# OBC_EBI_D-Latch.net
KiCad netlist of a schematic drawn in Altium Designer
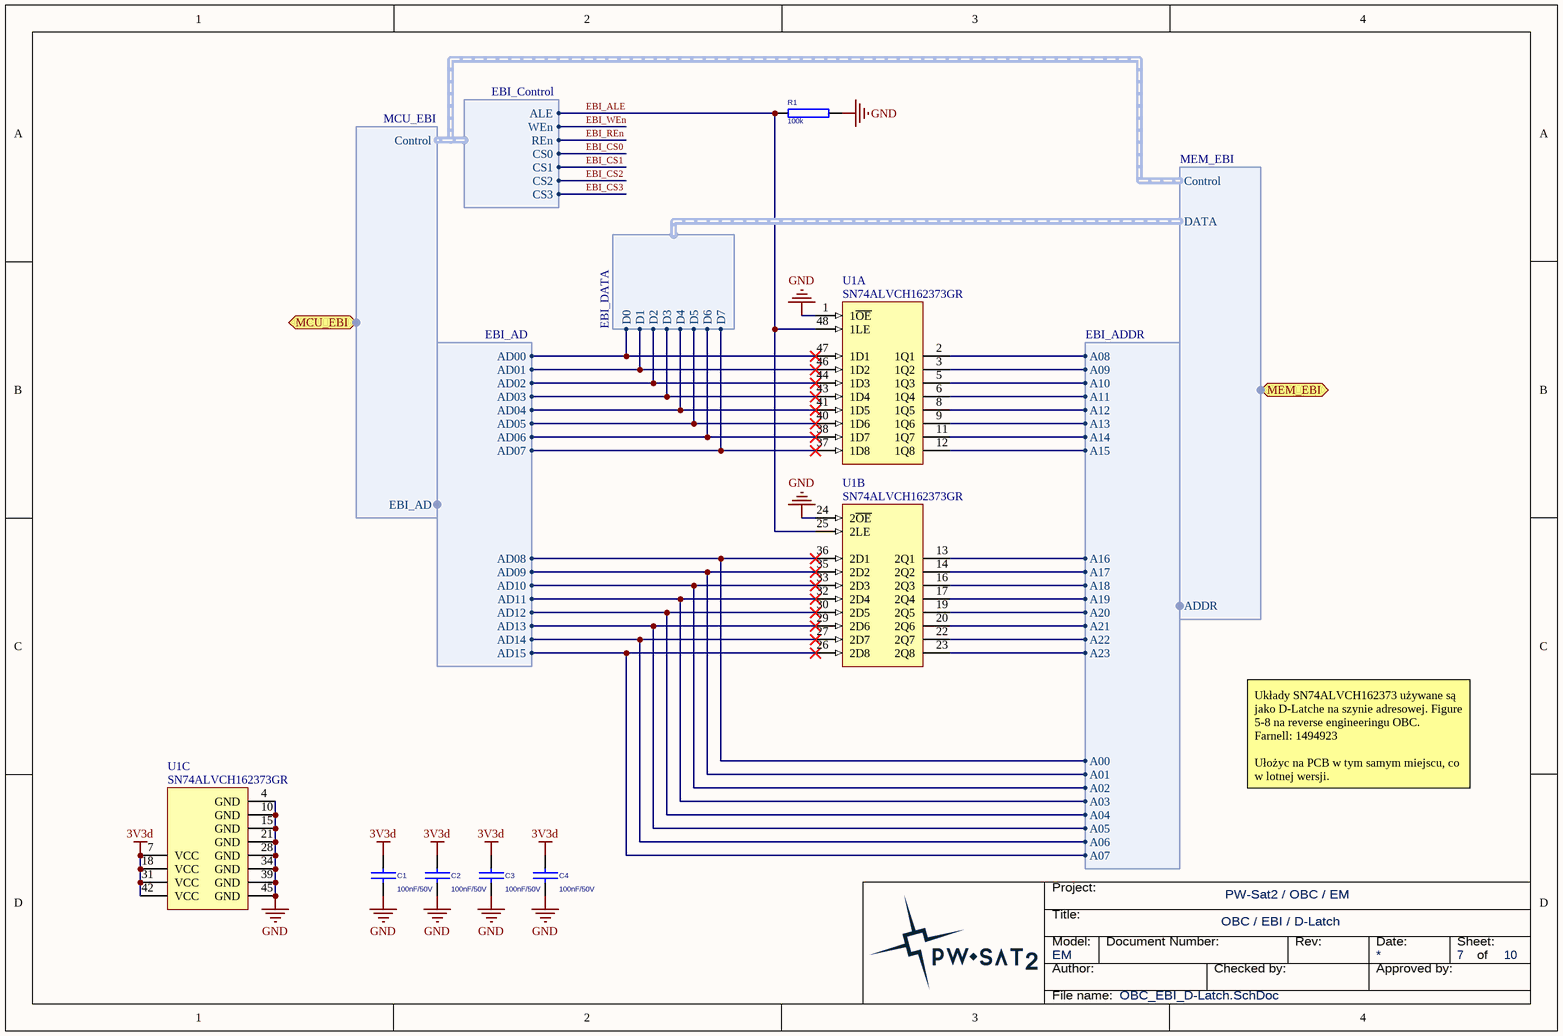
[diagram p0: OBC_EBI_D-Latch.SchDoc]

(export (version "E")
  (design (tool "Eeschema 10.0.6"))
  (components
    (comp (ref "C1")
      (value "100nF/50V")
      (footprint "C0603")
      (description "Capacitator")
      (fields (field (name "VOLTAGE") "50V"))
      (libsource (lib "SchLib") (part "CAP"))
    )
    (comp (ref "C2")
      (value "100nF/50V")
      (footprint "C0603")
      (description "Capacitator")
      (fields (field (name "VOLTAGE") "50V"))
      (libsource (lib "SchLib") (part "CAP"))
    )
    (comp (ref "C3")
      (value "100nF/50V")
      (footprint "C0603")
      (description "Capacitator")
      (fields (field (name "VOLTAGE") "50V"))
      (libsource (lib "SchLib") (part "CAP"))
    )
    (comp (ref "C4")
      (value "100nF/50V")
      (footprint "C0603")
      (description "Capacitator")
      (fields (field (name "VOLTAGE") "50V"))
      (libsource (lib "SchLib") (part "CAP"))
    )
    (comp (ref "R1")
      (value "100k")
      (footprint "R0603")
      (description "Resistor")
      (fields (field (name "TOLERANCE") "1%"))
      (libsource (lib "SchLib") (part "RES"))
    )
    (comp (ref "U1")
      (value "SN74ALVCH162373GR")
      (footprint "DGG0048A_N")
      (description "16-Bit Transparent D-Type Latch with 3-State Outputs, DGG0048A, LARGE T&R")
      (fields (field (name "MANUFACTURER") "Texas Instruments"))
      (libsource (lib "OBC") (part "SN74ALVCH162373GR"))
    )
  )
  (nets
    (net (code "5") (name "/A00") (class "Default")
      (node (ref "U1") (pin "36") (pinfunction "2D1_36") (pintype "input+no_connect"))
    )
    (net (code "6") (name "/A01") (class "Default")
      (node (ref "U1") (pin "35") (pinfunction "2D2_35") (pintype "input+no_connect"))
    )
    (net (code "7") (name "/A02") (class "Default")
      (node (ref "U1") (pin "33") (pinfunction "2D3_33") (pintype "input+no_connect"))
    )
    (net (code "8") (name "/A03") (class "Default")
      (node (ref "U1") (pin "32") (pinfunction "2D4_32") (pintype "input+no_connect"))
    )
    (net (code "9") (name "/A04") (class "Default")
      (node (ref "U1") (pin "30") (pinfunction "2D5_30") (pintype "input+no_connect"))
    )
    (net (code "10") (name "/A05") (class "Default")
      (node (ref "U1") (pin "29") (pinfunction "2D6_29") (pintype "input+no_connect"))
    )
    (net (code "11") (name "/A06") (class "Default")
      (node (ref "U1") (pin "27") (pinfunction "2D7_27") (pintype "input+no_connect"))
    )
    (net (code "12") (name "/A07") (class "Default")
      (node (ref "U1") (pin "26") (pinfunction "2D8_26") (pintype "input+no_connect"))
    )
    (net (code "13") (name "/A08") (class "Default")
      (node (ref "U1") (pin "2") (pinfunction "1Q1_2") (pintype "tri_state"))
    )
    (net (code "14") (name "/A09") (class "Default")
      (node (ref "U1") (pin "3") (pinfunction "1Q2_3") (pintype "tri_state"))
    )
    (net (code "15") (name "/A10") (class "Default")
      (node (ref "U1") (pin "5") (pinfunction "1Q3_5") (pintype "tri_state"))
    )
    (net (code "16") (name "/A11") (class "Default")
      (node (ref "U1") (pin "6") (pinfunction "1Q4_6") (pintype "tri_state"))
    )
    (net (code "17") (name "/A12") (class "Default")
      (node (ref "U1") (pin "8") (pinfunction "1Q5_8") (pintype "tri_state"))
    )
    (net (code "18") (name "/A13") (class "Default")
      (node (ref "U1") (pin "9") (pinfunction "1Q6_9") (pintype "tri_state"))
    )
    (net (code "19") (name "/A14") (class "Default")
      (node (ref "U1") (pin "11") (pinfunction "1Q7_11") (pintype "tri_state"))
    )
    (net (code "20") (name "/A15") (class "Default")
      (node (ref "U1") (pin "12") (pinfunction "1Q8_12") (pintype "tri_state"))
    )
    (net (code "21") (name "/A16") (class "Default")
      (node (ref "U1") (pin "13") (pinfunction "2Q1_13") (pintype "tri_state"))
    )
    (net (code "22") (name "/A17") (class "Default")
      (node (ref "U1") (pin "14") (pinfunction "2Q2_14") (pintype "tri_state"))
    )
    (net (code "23") (name "/A18") (class "Default")
      (node (ref "U1") (pin "16") (pinfunction "2Q3_16") (pintype "tri_state"))
    )
    (net (code "24") (name "/A19") (class "Default")
      (node (ref "U1") (pin "17") (pinfunction "2Q4_17") (pintype "tri_state"))
    )
    (net (code "25") (name "/A20") (class "Default")
      (node (ref "U1") (pin "19") (pinfunction "2Q5_19") (pintype "tri_state"))
    )
    (net (code "26") (name "/A21") (class "Default")
      (node (ref "U1") (pin "20") (pinfunction "2Q6_20") (pintype "tri_state"))
    )
    (net (code "27") (name "/A22") (class "Default")
      (node (ref "U1") (pin "22") (pinfunction "2Q7_22") (pintype "tri_state"))
    )
    (net (code "28") (name "/A23") (class "Default")
      (node (ref "U1") (pin "23") (pinfunction "2Q8_23") (pintype "tri_state"))
    )
    (net (code "29") (name "/AD00") (class "Default")
      (node (ref "U1") (pin "47") (pinfunction "1D1_47") (pintype "input+no_connect"))
    )
    (net (code "30") (name "/AD01") (class "Default")
      (node (ref "U1") (pin "46") (pinfunction "1D2_46") (pintype "input+no_connect"))
    )
    (net (code "31") (name "/AD02") (class "Default")
      (node (ref "U1") (pin "44") (pinfunction "1D3_44") (pintype "input+no_connect"))
    )
    (net (code "32") (name "/AD03") (class "Default")
      (node (ref "U1") (pin "43") (pinfunction "1D4_43") (pintype "input+no_connect"))
    )
    (net (code "33") (name "/AD04") (class "Default")
      (node (ref "U1") (pin "41") (pinfunction "1D5_41") (pintype "input+no_connect"))
    )
    (net (code "34") (name "/AD05") (class "Default")
      (node (ref "U1") (pin "40") (pinfunction "1D6_40") (pintype "input+no_connect"))
    )
    (net (code "35") (name "/AD06") (class "Default")
      (node (ref "U1") (pin "38") (pinfunction "1D7_38") (pintype "input+no_connect"))
    )
    (net (code "36") (name "/AD07") (class "Default")
      (node (ref "U1") (pin "37") (pinfunction "1D8_37") (pintype "input+no_connect"))
    )
    (net (code "37") (name "/EBI_ALE") (class "Default")
      (node (ref "R1") (pin "2") (pintype "passive"))
      (node (ref "U1") (pin "25") (pinfunction "2LE_25") (pintype "input"))
      (node (ref "U1") (pin "48") (pinfunction "1LE_48") (pintype "input"))
    )
    (net (code "48") (name "3V3d") (class "Default")
      (node (ref "C1") (pin "1") (pintype "passive"))
      (node (ref "C2") (pin "1") (pintype "passive"))
      (node (ref "C3") (pin "1") (pintype "passive"))
      (node (ref "C4") (pin "1") (pintype "passive"))
      (node (ref "U1") (pin "18") (pinfunction "VCC_18") (pintype "power_in"))
      (node (ref "U1") (pin "31") (pinfunction "VCC_31") (pintype "power_in"))
      (node (ref "U1") (pin "42") (pinfunction "VCC_42") (pintype "power_in"))
      (node (ref "U1") (pin "7") (pinfunction "VCC_7") (pintype "power_in"))
    )
    (net (code "49") (name "GND") (class "Default")
      (node (ref "C1") (pin "2") (pintype "passive"))
      (node (ref "C2") (pin "2") (pintype "passive"))
      (node (ref "C3") (pin "2") (pintype "passive"))
      (node (ref "C4") (pin "2") (pintype "passive"))
      (node (ref "R1") (pin "1") (pintype "passive"))
      (node (ref "U1") (pin "1") (pinfunction "1~{OE}_1") (pintype "input"))
      (node (ref "U1") (pin "10") (pinfunction "GND_10") (pintype "power_in"))
      (node (ref "U1") (pin "15") (pinfunction "GND_15") (pintype "power_in"))
      (node (ref "U1") (pin "21") (pinfunction "GND_21") (pintype "power_in"))
      (node (ref "U1") (pin "24") (pinfunction "2~{OE}_24") (pintype "input"))
      (node (ref "U1") (pin "28") (pinfunction "GND_28") (pintype "power_in"))
      (node (ref "U1") (pin "34") (pinfunction "GND_34") (pintype "power_in"))
      (node (ref "U1") (pin "39") (pinfunction "GND_39") (pintype "power_in"))
      (node (ref "U1") (pin "4") (pinfunction "GND_4") (pintype "power_in"))
      (node (ref "U1") (pin "45") (pinfunction "GND_45") (pintype "power_in"))
    )
  )
)
